# untitled.net
KiCad netlist of a schematic drawn in EAGLE
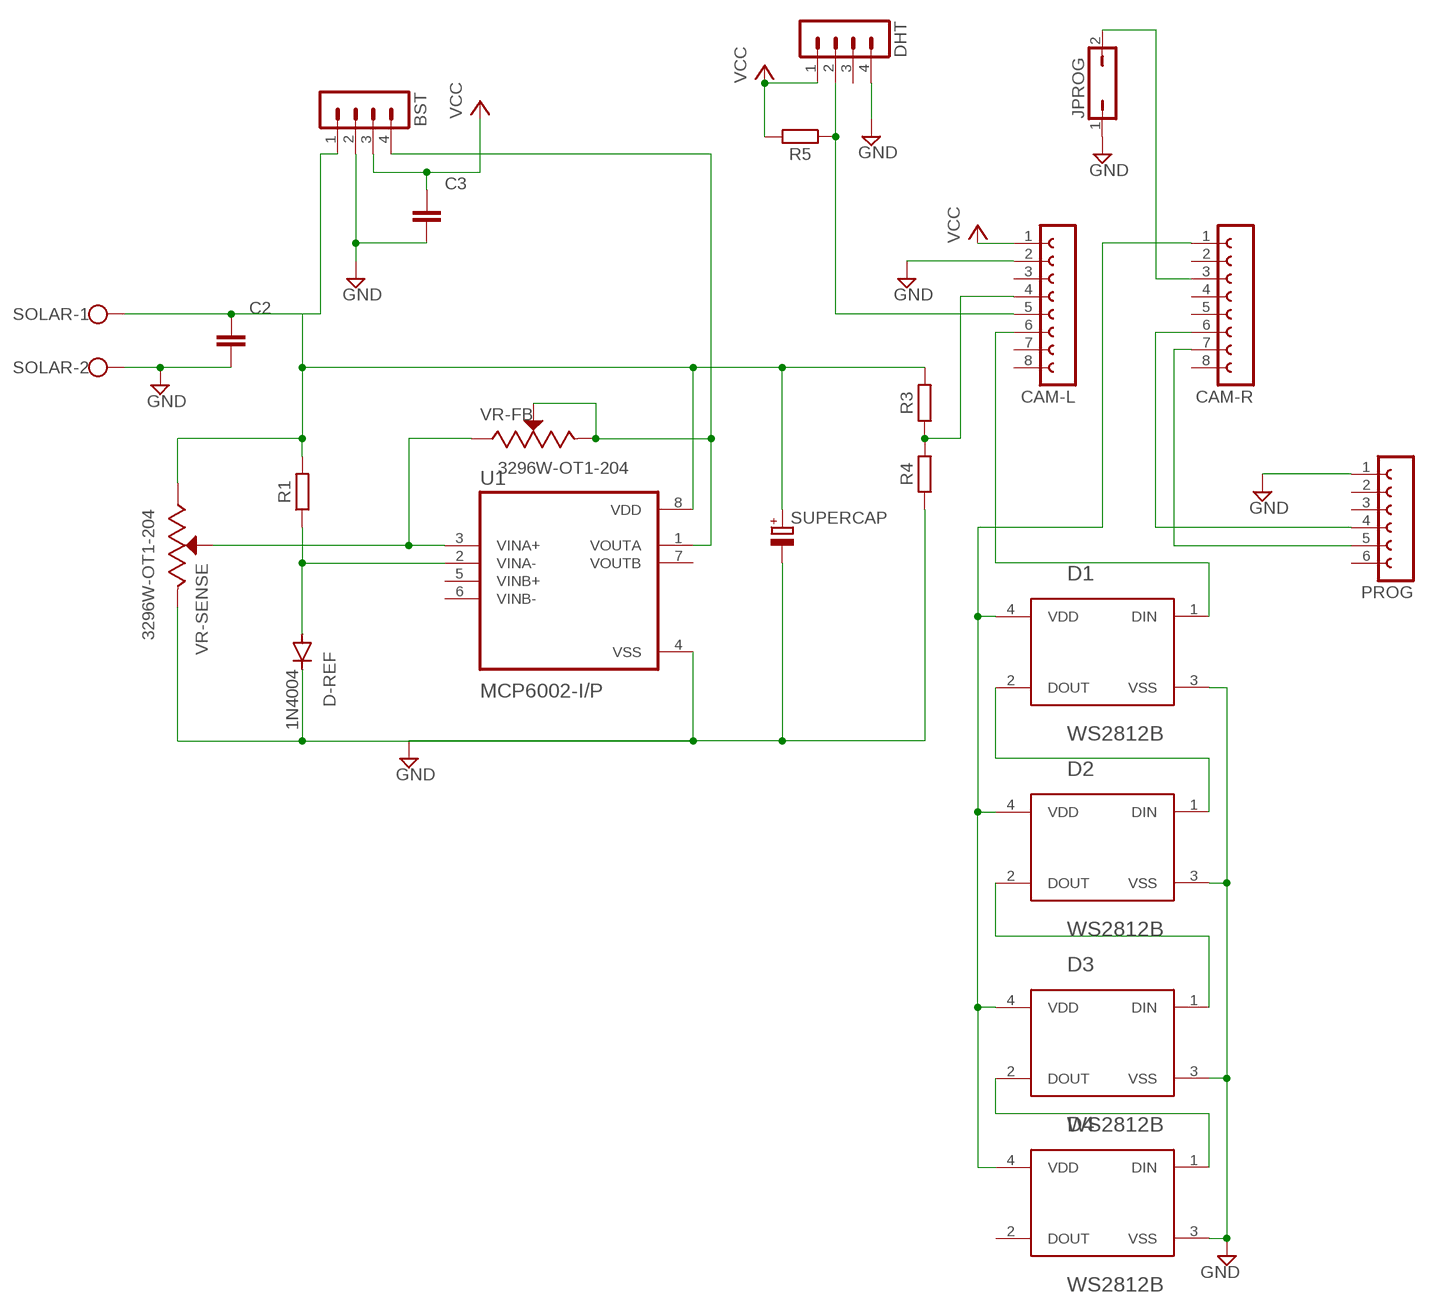
[diagram p0: schematic, sheet 1]

(export (version "E")
  (design (tool "Eeschema 10.0.6"))
  (components
    (comp (ref "BST")
      (value "MA04-1")
      (footprint "eagle-import:MA04-1")
      (libsource (lib "eagle-import") (part "MA04-1"))
    )
    (comp (ref "C2")
      (value "C_RADIAL-12.5MM-DIA")
      (footprint "eagle-import:CAPRD550W60D1025H1250B")
      (libsource (lib "eagle-import") (part "CRADIAL-12.5MM-DIA_"))
    )
    (comp (ref "C3")
      (value "C_RADIAL-12.5MM-DIA")
      (footprint "eagle-import:CAPRD550W60D1025H1250B")
      (libsource (lib "eagle-import") (part "CRADIAL-12.5MM-DIA_"))
    )
    (comp (ref "CAM-L")
      (value "FE08-1")
      (footprint "eagle-import:FE08")
      (libsource (lib "eagle-import") (part "FE08-1"))
    )
    (comp (ref "CAM-R")
      (value "FE08-1")
      (footprint "eagle-import:FE08")
      (libsource (lib "eagle-import") (part "FE08-1"))
    )
    (comp (ref "D-REF")
      (value "1N4004")
      (footprint "eagle-import:DO41-10")
      (libsource (lib "eagle-import") (part "1N4004"))
    )
    (comp (ref "D1")
      (value "WS2812B")
      (footprint "eagle-import:5050")
      (fields (field (name "MF") "Adafruit Industries") (field (name "MP") "ADA1655"))
      (libsource (lib "eagle-import") (part "WS2812B"))
    )
    (comp (ref "D2")
      (value "WS2812B")
      (footprint "eagle-import:5050")
      (fields (field (name "MF") "Adafruit Industries") (field (name "MP") "ADA1655"))
      (libsource (lib "eagle-import") (part "WS2812B"))
    )
    (comp (ref "D3")
      (value "WS2812B")
      (footprint "eagle-import:5050")
      (fields (field (name "MF") "Adafruit Industries") (field (name "MP") "ADA1655"))
      (libsource (lib "eagle-import") (part "WS2812B"))
    )
    (comp (ref "D4")
      (value "WS2812B")
      (footprint "eagle-import:5050")
      (fields (field (name "MF") "Adafruit Industries") (field (name "MP") "ADA1655"))
      (libsource (lib "eagle-import") (part "WS2812B"))
    )
    (comp (ref "DHT")
      (value "MA04-1")
      (footprint "eagle-import:MA04-1")
      (libsource (lib "eagle-import") (part "MA04-1"))
    )
    (comp (ref "JPROG")
      (value "JP1Q")
      (footprint "eagle-import:JP1")
      (libsource (lib "eagle-import") (part "JP1Q"))
    )
    (comp (ref "PROG")
      (value "FE06-1")
      (footprint "eagle-import:FE06")
      (libsource (lib "eagle-import") (part "FE06-1"))
    )
    (comp (ref "R1")
      (value "R_AXIAL-7.2MM-PITCH")
      (footprint "eagle-import:RESAD724W46L381D178B")
      (libsource (lib "eagle-import") (part "RAXIAL-7.2MM-PITCH_"))
    )
    (comp (ref "R3")
      (value "R_AXIAL-7.2MM-PITCH")
      (footprint "eagle-import:RESAD724W46L381D178B")
      (libsource (lib "eagle-import") (part "RAXIAL-7.2MM-PITCH_"))
    )
    (comp (ref "R4")
      (value "R_AXIAL-7.2MM-PITCH")
      (footprint "eagle-import:RESAD724W46L381D178B")
      (libsource (lib "eagle-import") (part "RAXIAL-7.2MM-PITCH_"))
    )
    (comp (ref "R5")
      (value "R_AXIAL-7.2MM-PITCH")
      (footprint "eagle-import:RESAD724W46L381D178B")
      (libsource (lib "eagle-import") (part "RAXIAL-7.2MM-PITCH_"))
    )
    (comp (ref "SOLAR")
      (value "W237-102")
      (footprint "eagle-import:W237-102")
      (fields (field (name "MPN") "237-102"))
      (libsource (lib "eagle-import") (part "W237-102"))
    )
    (comp (ref "SUPERCAP")
      (value "C-POL_RADIAL-32MM-DIA")
      (footprint "eagle-import:CAPPRD1000W100D2275H3200B")
      (libsource (lib "eagle-import") (part "C-POLRADIAL-32MM-DIA_"))
    )
    (comp (ref "U1")
      (value "MCP6002-I/P")
      (footprint "eagle-import:DIP787W46P254L927H533Q8")
      (fields (field (name "MF") "Microchip"))
      (libsource (lib "eagle-import") (part "MCP6002-I/P"))
    )
    (comp (ref "VR-FB")
      (value "3296W-OT1-204")
      (footprint "eagle-import:TRIM_3296W-OT1-204")
      (fields (field (name "MF") "Bourns"))
      (libsource (lib "eagle-import") (part "3296W-OT1-204"))
    )
    (comp (ref "VR-SENSE")
      (value "3296W-OT1-204")
      (footprint "eagle-import:TRIM_3296W-OT1-204")
      (fields (field (name "MF") "Bourns"))
      (libsource (lib "eagle-import") (part "3296W-OT1-204"))
    )
  )
  (nets
    (net (code "1") (name "GND") (class "Default")
      (node (ref "BST") (pin "2") (pinfunction "2_2") (pintype "passive"))
      (node (ref "C2") (pin "2") (pinfunction "2_2") (pintype "passive"))
      (node (ref "C3") (pin "2") (pinfunction "2_2") (pintype "passive"))
      (node (ref "CAM-L") (pin "2") (pinfunction "2_2") (pintype "passive"))
      (node (ref "D-REF") (pin "C") (pinfunction "C_C") (pintype "passive"))
      (node (ref "D1") (pin "3") (pinfunction "VSS_3") (pintype "power_in"))
      (node (ref "D2") (pin "3") (pinfunction "VSS_3") (pintype "power_in"))
      (node (ref "D3") (pin "3") (pinfunction "VSS_3") (pintype "power_in"))
      (node (ref "D4") (pin "3") (pinfunction "VSS_3") (pintype "power_in"))
      (node (ref "DHT") (pin "4") (pinfunction "4_4") (pintype "passive"))
      (node (ref "JPROG") (pin "1") (pinfunction "1_1") (pintype "passive"))
      (node (ref "PROG") (pin "1") (pinfunction "1_1") (pintype "passive"))
      (node (ref "R4") (pin "1") (pinfunction "1_1") (pintype "passive"))
      (node (ref "SOLAR") (pin "2") (pinfunction "KL_2") (pintype "passive"))
      (node (ref "SUPERCAP") (pin "2") (pinfunction "-_2") (pintype "passive"))
      (node (ref "U1") (pin "4") (pinfunction "VSS_4") (pintype "power_in"))
      (node (ref "VR-SENSE") (pin "3") (pinfunction "CW_3") (pintype "passive"))
    )
    (net (code "2") (name "Net-(CAM-L-Pad4)") (class "Default")
      (node (ref "CAM-L") (pin "4") (pinfunction "4_4") (pintype "passive"))
      (node (ref "R3") (pin "1") (pinfunction "1_1") (pintype "passive"))
      (node (ref "R4") (pin "2") (pinfunction "2_2") (pintype "passive"))
    )
    (net (code "3") (name "Net-(CAM-L-Pad5)") (class "Default")
      (node (ref "CAM-L") (pin "5") (pinfunction "5_5") (pintype "passive"))
      (node (ref "DHT") (pin "2") (pinfunction "2_2") (pintype "passive"))
      (node (ref "R5") (pin "1") (pinfunction "1_1") (pintype "passive"))
    )
    (net (code "4") (name "Net-(CAM-R-Pad3)") (class "Default")
      (node (ref "CAM-R") (pin "3") (pinfunction "3_3") (pintype "passive"))
      (node (ref "JPROG") (pin "2") (pinfunction "2_2") (pintype "passive"))
    )
    (net (code "5") (name "Net-(CAM-R-Pad6)") (class "Default")
      (node (ref "CAM-R") (pin "6") (pinfunction "6_6") (pintype "passive"))
      (node (ref "PROG") (pin "4") (pinfunction "4_4") (pintype "passive"))
    )
    (net (code "6") (name "Net-(CAM-R-Pad7)") (class "Default")
      (node (ref "CAM-R") (pin "7") (pinfunction "7_7") (pintype "passive"))
      (node (ref "PROG") (pin "5") (pinfunction "5_5") (pintype "passive"))
    )
    (net (code "7") (name "Net-(D1-DIN)") (class "Default")
      (node (ref "CAM-L") (pin "6") (pinfunction "6_6") (pintype "passive"))
      (node (ref "D1") (pin "1") (pinfunction "DIN_1") (pintype "input"))
    )
    (net (code "8") (name "Net-(D1-DOUT)") (class "Default")
      (node (ref "D1") (pin "2") (pinfunction "DOUT_2") (pintype "output"))
      (node (ref "D2") (pin "1") (pinfunction "DIN_1") (pintype "input"))
    )
    (net (code "9") (name "Net-(D1-VDD)") (class "Default")
      (node (ref "CAM-R") (pin "1") (pinfunction "1_1") (pintype "passive"))
      (node (ref "D1") (pin "4") (pinfunction "VDD_4") (pintype "power_in"))
      (node (ref "D2") (pin "4") (pinfunction "VDD_4") (pintype "power_in"))
      (node (ref "D3") (pin "4") (pinfunction "VDD_4") (pintype "power_in"))
      (node (ref "D4") (pin "4") (pinfunction "VDD_4") (pintype "power_in"))
    )
    (net (code "10") (name "Net-(D2-DOUT)") (class "Default")
      (node (ref "D2") (pin "2") (pinfunction "DOUT_2") (pintype "output"))
      (node (ref "D3") (pin "1") (pinfunction "DIN_1") (pintype "input"))
    )
    (net (code "11") (name "Net-(D3-DOUT)") (class "Default")
      (node (ref "D3") (pin "2") (pinfunction "DOUT_2") (pintype "output"))
      (node (ref "D4") (pin "1") (pinfunction "DIN_1") (pintype "input"))
    )
    (net (code "12") (name "Net-(SOLARA-KL)") (class "Default")
      (node (ref "BST") (pin "1") (pinfunction "1_1") (pintype "passive"))
      (node (ref "C2") (pin "1") (pinfunction "1_1") (pintype "passive"))
      (node (ref "R1") (pin "2") (pinfunction "2_2") (pintype "passive"))
      (node (ref "R3") (pin "2") (pinfunction "2_2") (pintype "passive"))
      (node (ref "SOLAR") (pin "1") (pinfunction "KL_1") (pintype "passive"))
      (node (ref "SUPERCAP") (pin "1") (pinfunction "+_1") (pintype "passive"))
      (node (ref "U1") (pin "8") (pinfunction "VDD_8") (pintype "power_in"))
      (node (ref "VR-SENSE") (pin "1") (pinfunction "CCW_1") (pintype "passive"))
    )
    (net (code "13") (name "Net-(U1-VINA+)") (class "Default")
      (node (ref "U1") (pin "3") (pinfunction "VINA+_3") (pintype "input"))
      (node (ref "VR-FB") (pin "1") (pinfunction "CCW_1") (pintype "passive"))
      (node (ref "VR-SENSE") (pin "2") (pinfunction "WIPER_2") (pintype "passive"))
    )
    (net (code "14") (name "Net-(U1-VINA-)") (class "Default")
      (node (ref "D-REF") (pin "A") (pinfunction "A_A") (pintype "passive"))
      (node (ref "R1") (pin "1") (pinfunction "1_1") (pintype "passive"))
      (node (ref "U1") (pin "2") (pinfunction "VINA-_2") (pintype "input"))
    )
    (net (code "15") (name "Net-(U1-VOUTA)") (class "Default")
      (node (ref "BST") (pin "4") (pinfunction "4_4") (pintype "passive"))
      (node (ref "U1") (pin "1") (pinfunction "VOUTA_1") (pintype "output"))
      (node (ref "VR-FB") (pin "2") (pinfunction "WIPER_2") (pintype "passive"))
      (node (ref "VR-FB") (pin "3") (pinfunction "CW_3") (pintype "passive"))
    )
    (net (code "16") (name "VCC") (class "Default")
      (node (ref "BST") (pin "3") (pinfunction "3_3") (pintype "passive"))
      (node (ref "C3") (pin "1") (pinfunction "1_1") (pintype "passive"))
      (node (ref "CAM-L") (pin "1") (pinfunction "1_1") (pintype "passive"))
      (node (ref "DHT") (pin "1") (pinfunction "1_1") (pintype "passive"))
      (node (ref "R5") (pin "2") (pinfunction "2_2") (pintype "passive"))
    )
    (net (code "17") (name "unconnected-(CAM-L-Pad3)") (class "Default")
      (node (ref "CAM-L") (pin "3") (pinfunction "3_3") (pintype "passive"))
    )
    (net (code "18") (name "unconnected-(CAM-L-Pad7)") (class "Default")
      (node (ref "CAM-L") (pin "7") (pinfunction "7_7") (pintype "passive"))
    )
    (net (code "19") (name "unconnected-(CAM-L-Pad8)") (class "Default")
      (node (ref "CAM-L") (pin "8") (pinfunction "8_8") (pintype "passive"))
    )
    (net (code "20") (name "unconnected-(CAM-R-Pad2)") (class "Default")
      (node (ref "CAM-R") (pin "2") (pinfunction "2_2") (pintype "passive"))
    )
    (net (code "21") (name "unconnected-(CAM-R-Pad4)") (class "Default")
      (node (ref "CAM-R") (pin "4") (pinfunction "4_4") (pintype "passive"))
    )
    (net (code "22") (name "unconnected-(CAM-R-Pad5)") (class "Default")
      (node (ref "CAM-R") (pin "5") (pinfunction "5_5") (pintype "passive"))
    )
    (net (code "23") (name "unconnected-(CAM-R-Pad8)") (class "Default")
      (node (ref "CAM-R") (pin "8") (pinfunction "8_8") (pintype "passive"))
    )
    (net (code "24") (name "unconnected-(D4-DOUT-Pad2)") (class "Default")
      (node (ref "D4") (pin "2") (pinfunction "DOUT_2") (pintype "output"))
    )
    (net (code "25") (name "unconnected-(DHT-Pad3)") (class "Default")
      (node (ref "DHT") (pin "3") (pinfunction "3_3") (pintype "passive"))
    )
    (net (code "26") (name "unconnected-(PROG-Pad2)") (class "Default")
      (node (ref "PROG") (pin "2") (pinfunction "2_2") (pintype "passive"))
    )
    (net (code "27") (name "unconnected-(PROG-Pad3)") (class "Default")
      (node (ref "PROG") (pin "3") (pinfunction "3_3") (pintype "passive"))
    )
    (net (code "28") (name "unconnected-(PROG-Pad6)") (class "Default")
      (node (ref "PROG") (pin "6") (pinfunction "6_6") (pintype "passive"))
    )
    (net (code "29") (name "unconnected-(U1-VINB+-Pad5)") (class "Default")
      (node (ref "U1") (pin "5") (pinfunction "VINB+_5") (pintype "input"))
    )
    (net (code "30") (name "unconnected-(U1-VINB--Pad6)") (class "Default")
      (node (ref "U1") (pin "6") (pinfunction "VINB-_6") (pintype "input"))
    )
    (net (code "31") (name "unconnected-(U1-VOUTB-Pad7)") (class "Default")
      (node (ref "U1") (pin "7") (pinfunction "VOUTB_7") (pintype "output"))
    )
  )
)
